# WIFI-BT.net
KiCad netlist of a schematic drawn in Altium Designer
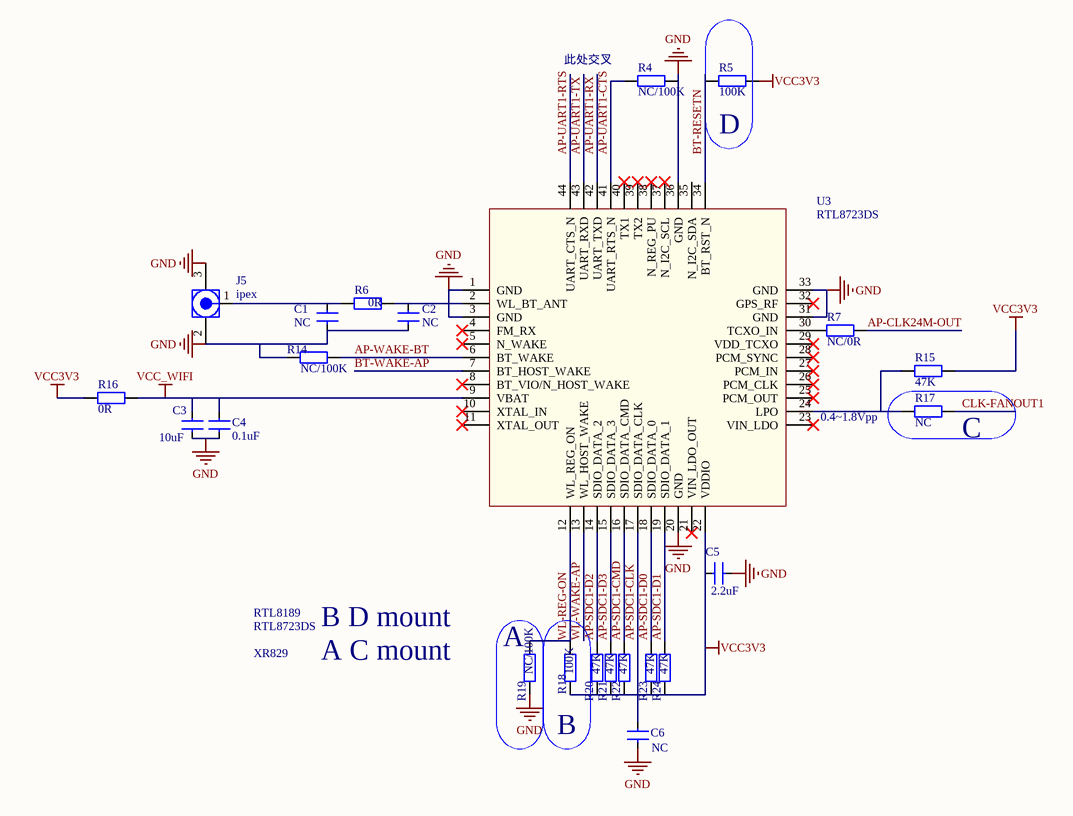
[diagram p0: WIFI-BT.SchDoc]

(export (version "E")
  (design (tool "Eeschema 10.0.6"))
  (components
    (comp (ref "C1")
      (value "NC")
      (footprint "C0402")
      (description "普通小电容")
      (libsource (lib "LIB_MANGO") (part "CAP"))
    )
    (comp (ref "C2")
      (value "NC")
      (footprint "C0402")
      (description "普通小电容")
      (libsource (lib "LIB_MANGO") (part "CAP"))
    )
    (comp (ref "C3")
      (value "10uF")
      (footprint "C0402")
      (description "普通小电容")
      (libsource (lib "LIB_MANGO") (part "CAP"))
    )
    (comp (ref "C4")
      (value "0.1uF")
      (footprint "C0402")
      (description "普通小电容")
      (libsource (lib "LIB_MANGO") (part "CAP"))
    )
    (comp (ref "C5")
      (value "2.2uF")
      (footprint "C0402")
      (description "普通小电容")
      (libsource (lib "LIB_MANGO") (part "CAP"))
    )
    (comp (ref "C6")
      (value "NC")
      (footprint "C0402")
      (description "普通小电容")
      (libsource (lib "LIB_MANGO") (part "CAP"))
    )
    (comp (ref "J5")
      (value "ipex")
      (footprint "I-PEX SOCKET")
      (libsource (lib "LIB_MANGO") (part "MCX_IPEX"))
    )
    (comp (ref "R4")
      (value "NC/100K")
      (footprint "R0402")
      (description "普通电阻")
      (libsource (lib "") (part "RES_1"))
    )
    (comp (ref "R5")
      (value "100K")
      (footprint "R0402")
      (description "普通电阻")
      (libsource (lib "") (part "RES_1"))
    )
    (comp (ref "R6")
      (value "0R")
      (footprint "R0402")
      (description "普通电阻")
      (libsource (lib "") (part "RES_2"))
    )
    (comp (ref "R7")
      (value "NC/0R")
      (footprint "R0402")
      (description "普通电阻")
      (libsource (lib "") (part "RES_2"))
    )
    (comp (ref "R14")
      (value "NC/100K")
      (footprint "R0402")
      (description "普通电阻")
      (libsource (lib "") (part "RES_2"))
    )
    (comp (ref "R15")
      (value "47K")
      (footprint "R0402")
      (description "普通电阻")
      (libsource (lib "LIB_MANGO") (part "RES"))
    )
    (comp (ref "R16")
      (value "0R")
      (footprint "R0402")
      (description "普通电阻")
      (libsource (lib "") (part "RES_2"))
    )
    (comp (ref "R17")
      (value "NC")
      (footprint "R0402")
      (description "普通电阻")
      (libsource (lib "") (part "RES_1"))
    )
    (comp (ref "R18")
      (value "100K")
      (footprint "R0402")
      (description "普通电阻")
      (libsource (lib "LIB_MANGO") (part "RES"))
    )
    (comp (ref "R19")
      (value "NC/100K")
      (footprint "R0402")
      (description "普通电阻")
      (libsource (lib "LIB_MANGO") (part "RES"))
    )
    (comp (ref "R20")
      (value "47K")
      (footprint "R0402")
      (description "普通电阻")
      (libsource (lib "LIB_MANGO") (part "RES"))
    )
    (comp (ref "R21")
      (value "47K")
      (footprint "R0402")
      (description "普通电阻")
      (libsource (lib "LIB_MANGO") (part "RES"))
    )
    (comp (ref "R22")
      (value "47K")
      (footprint "R0402")
      (description "普通电阻")
      (libsource (lib "LIB_MANGO") (part "RES"))
    )
    (comp (ref "R23")
      (value "47K")
      (footprint "R0402")
      (description "普通电阻")
      (libsource (lib "LIB_MANGO") (part "RES"))
    )
    (comp (ref "R24")
      (value "47K")
      (footprint "R0402")
      (description "普通电阻")
      (libsource (lib "LIB_MANGO") (part "RES"))
    )
    (comp (ref "U3") (value "RTL8723DS") (footprint "RTL8723DS") (libsource (lib "A") (part "AP6212")))
  )
  (nets
    (net (code "1") (name "/AP-CLK24M-OUT") (class "Default")
      (node (ref "R7") (pin "1") (pinfunction "1_1") (pintype "passive"))
    )
    (net (code "2") (name "/AP-SDC1-CLK") (class "Default")
      (node (ref "C6") (pin "2") (pinfunction "2_2") (pintype "passive"))
      (node (ref "U3") (pin "17") (pinfunction "SDIO_DATA_CLK_17") (pintype "passive"))
    )
    (net (code "3") (name "/AP-SDC1-CMD") (class "Default")
      (node (ref "R22") (pin "2") (pinfunction "2_2") (pintype "passive"))
      (node (ref "U3") (pin "16") (pinfunction "SDIO_DATA_CMD_16") (pintype "passive"))
    )
    (net (code "4") (name "/AP-SDC1-D0") (class "Default")
      (node (ref "R23") (pin "2") (pinfunction "2_2") (pintype "passive"))
      (node (ref "U3") (pin "18") (pinfunction "SDIO_DATA_0_18") (pintype "passive"))
    )
    (net (code "5") (name "/AP-SDC1-D1") (class "Default")
      (node (ref "R24") (pin "2") (pinfunction "2_2") (pintype "passive"))
      (node (ref "U3") (pin "19") (pinfunction "SDIO_DATA_1_19") (pintype "passive"))
    )
    (net (code "6") (name "/AP-SDC1-D2") (class "Default")
      (node (ref "R20") (pin "2") (pinfunction "2_2") (pintype "passive"))
      (node (ref "U3") (pin "14") (pinfunction "SDIO_DATA_2_14") (pintype "passive"))
    )
    (net (code "7") (name "/AP-SDC1-D3") (class "Default")
      (node (ref "R21") (pin "2") (pinfunction "2_2") (pintype "passive"))
      (node (ref "U3") (pin "15") (pinfunction "SDIO_DATA_3_15") (pintype "passive"))
    )
    (net (code "8") (name "/AP-UART1-CTS") (class "Default")
      (node (ref "R4") (pin "2") (pinfunction "2_2") (pintype "passive"))
      (node (ref "U3") (pin "41") (pinfunction "UART_RTS_N_41") (pintype "passive"))
    )
    (net (code "9") (name "/AP-UART1-RTS") (class "Default")
      (node (ref "U3") (pin "44") (pinfunction "UART_CTS_N_44") (pintype "passive"))
    )
    (net (code "10") (name "/AP-UART1-RX") (class "Default")
      (node (ref "U3") (pin "42") (pinfunction "UART_TXD_42") (pintype "passive"))
    )
    (net (code "11") (name "/AP-UART1-TX") (class "Default")
      (node (ref "U3") (pin "43") (pinfunction "UART_RXD_43") (pintype "passive"))
    )
    (net (code "12") (name "/AP-WAKE-BT") (class "Default")
      (node (ref "R14") (pin "1") (pinfunction "1_1") (pintype "passive"))
      (node (ref "U3") (pin "6") (pinfunction "BT_WAKE_6") (pintype "passive"))
    )
    (net (code "13") (name "/BT-RESETN") (class "Default")
      (node (ref "R5") (pin "2") (pinfunction "2_2") (pintype "passive"))
      (node (ref "U3") (pin "34") (pinfunction "BT_RST_N_34") (pintype "passive"))
    )
    (net (code "14") (name "/BT-WAKE-AP") (class "Default")
      (node (ref "U3") (pin "7") (pinfunction "BT_HOST_WAKE_7") (pintype "passive"))
    )
    (net (code "15") (name "/CLK-FANOUT1") (class "Default")
      (node (ref "R17") (pin "1") (pinfunction "1_1") (pintype "passive"))
    )
    (net (code "16") (name "/WL-REG-ON") (class "Default")
      (node (ref "R18") (pin "2") (pinfunction "2_2") (pintype "passive"))
      (node (ref "R19") (pin "2") (pinfunction "2_2") (pintype "passive"))
      (node (ref "U3") (pin "12") (pinfunction "WL_REG_ON_12") (pintype "passive"))
    )
    (net (code "17") (name "/WL-WAKE-AP") (class "Default")
      (node (ref "U3") (pin "13") (pinfunction "WL_HOST_WAKE_13") (pintype "passive"))
    )
    (net (code "18") (name "GND") (class "Default")
      (node (ref "C1") (pin "1") (pinfunction "1_1") (pintype "passive"))
      (node (ref "C2") (pin "1") (pinfunction "1_1") (pintype "passive"))
      (node (ref "C3") (pin "1") (pinfunction "1_1") (pintype "passive"))
      (node (ref "C4") (pin "1") (pinfunction "1_1") (pintype "passive"))
      (node (ref "C5") (pin "1") (pinfunction "1_1") (pintype "passive"))
      (node (ref "C6") (pin "1") (pinfunction "1_1") (pintype "passive"))
      (node (ref "J5") (pin "2") (pinfunction "GND_2") (pintype "power_in"))
      (node (ref "J5") (pin "3") (pinfunction "GND_3") (pintype "power_in"))
      (node (ref "R14") (pin "2") (pinfunction "2_2") (pintype "passive"))
      (node (ref "R19") (pin "1") (pinfunction "1_1") (pintype "passive"))
      (node (ref "R4") (pin "1") (pinfunction "1_1") (pintype "passive"))
      (node (ref "U3") (pin "1") (pinfunction "GND_1") (pintype "passive"))
      (node (ref "U3") (pin "20") (pinfunction "GND_20") (pintype "passive"))
      (node (ref "U3") (pin "3") (pinfunction "GND_3") (pintype "passive"))
      (node (ref "U3") (pin "31") (pinfunction "GND_31") (pintype "passive"))
      (node (ref "U3") (pin "33") (pinfunction "GND_33") (pintype "passive"))
      (node (ref "U3") (pin "36") (pinfunction "GND_36") (pintype "passive"))
    )
    (net (code "19") (name "Net-(J5-Signal)") (class "Default")
      (node (ref "C1") (pin "2") (pinfunction "2_2") (pintype "passive"))
      (node (ref "J5") (pin "1") (pinfunction "Signal_1") (pintype "passive"))
      (node (ref "R6") (pin "2") (pinfunction "2_2") (pintype "passive"))
    )
    (net (code "20") (name "Net-(U3-LPO)") (class "Default")
      (node (ref "R15") (pin "1") (pinfunction "1_1") (pintype "passive"))
      (node (ref "R17") (pin "2") (pinfunction "2_2") (pintype "passive"))
      (node (ref "U3") (pin "24") (pinfunction "LPO_24") (pintype "passive"))
    )
    (net (code "21") (name "Net-(U3-TCXO_IN)") (class "Default")
      (node (ref "R7") (pin "2") (pinfunction "2_2") (pintype "passive"))
      (node (ref "U3") (pin "30") (pinfunction "TCXO_IN_30") (pintype "passive"))
    )
    (net (code "22") (name "Net-(U3-WL_BT_ANT)") (class "Default")
      (node (ref "C2") (pin "2") (pinfunction "2_2") (pintype "passive"))
      (node (ref "R6") (pin "1") (pinfunction "1_1") (pintype "passive"))
      (node (ref "U3") (pin "2") (pinfunction "WL_BT_ANT_2") (pintype "passive"))
    )
    (net (code "23") (name "VCC3V3") (class "Default")
      (node (ref "C5") (pin "2") (pinfunction "2_2") (pintype "passive"))
      (node (ref "R15") (pin "2") (pinfunction "2_2") (pintype "passive"))
      (node (ref "R16") (pin "2") (pinfunction "2_2") (pintype "passive"))
      (node (ref "R18") (pin "1") (pinfunction "1_1") (pintype "passive"))
      (node (ref "R20") (pin "1") (pinfunction "1_1") (pintype "passive"))
      (node (ref "R21") (pin "1") (pinfunction "1_1") (pintype "passive"))
      (node (ref "R22") (pin "1") (pinfunction "1_1") (pintype "passive"))
      (node (ref "R23") (pin "1") (pinfunction "1_1") (pintype "passive"))
      (node (ref "R24") (pin "1") (pinfunction "1_1") (pintype "passive"))
      (node (ref "R5") (pin "1") (pinfunction "1_1") (pintype "passive"))
      (node (ref "U3") (pin "22") (pinfunction "VDDIO_22") (pintype "passive"))
    )
    (net (code "24") (name "VCC_WIFI") (class "Default")
      (node (ref "C3") (pin "2") (pinfunction "2_2") (pintype "passive"))
      (node (ref "C4") (pin "2") (pinfunction "2_2") (pintype "passive"))
      (node (ref "R16") (pin "1") (pinfunction "1_1") (pintype "passive"))
      (node (ref "U3") (pin "9") (pinfunction "VBAT_9") (pintype "passive"))
    )
    (net (code "25") (name "unconnected-(U3-BT_VIO{slash}N_HOST_WAKE-Pad8)") (class "Default")
      (node (ref "U3") (pin "8") (pinfunction "BT_VIO/N_HOST_WAKE_8") (pintype "passive+no_connect"))
    )
    (net (code "26") (name "unconnected-(U3-FM_RX-Pad4)") (class "Default")
      (node (ref "U3") (pin "4") (pinfunction "FM_RX_4") (pintype "passive+no_connect"))
    )
    (net (code "27") (name "unconnected-(U3-GPS_RF-Pad32)") (class "Default")
      (node (ref "U3") (pin "32") (pinfunction "GPS_RF_32") (pintype "passive+no_connect"))
    )
    (net (code "28") (name "unconnected-(U3-N_I2C_SCL-Pad37)") (class "Default")
      (node (ref "U3") (pin "37") (pinfunction "N_I2C_SCL_37") (pintype "passive+no_connect"))
    )
    (net (code "29") (name "unconnected-(U3-N_I2C_SDA-Pad35)") (class "Default")
      (node (ref "U3") (pin "35") (pinfunction "N_I2C_SDA_35") (pintype "passive"))
    )
    (net (code "30") (name "unconnected-(U3-N_REG_PU-Pad38)") (class "Default")
      (node (ref "U3") (pin "38") (pinfunction "N_REG_PU_38") (pintype "passive+no_connect"))
    )
    (net (code "31") (name "unconnected-(U3-N_WAKE-Pad5)") (class "Default")
      (node (ref "U3") (pin "5") (pinfunction "N_WAKE_5") (pintype "passive+no_connect"))
    )
    (net (code "32") (name "unconnected-(U3-PCM_CLK-Pad26)") (class "Default")
      (node (ref "U3") (pin "26") (pinfunction "PCM_CLK_26") (pintype "passive+no_connect"))
    )
    (net (code "33") (name "unconnected-(U3-PCM_IN-Pad27)") (class "Default")
      (node (ref "U3") (pin "27") (pinfunction "PCM_IN_27") (pintype "passive+no_connect"))
    )
    (net (code "34") (name "unconnected-(U3-PCM_OUT-Pad25)") (class "Default")
      (node (ref "U3") (pin "25") (pinfunction "PCM_OUT_25") (pintype "passive+no_connect"))
    )
    (net (code "35") (name "unconnected-(U3-PCM_SYNC-Pad28)") (class "Default")
      (node (ref "U3") (pin "28") (pinfunction "PCM_SYNC_28") (pintype "passive+no_connect"))
    )
    (net (code "36") (name "unconnected-(U3-TX1-Pad40)") (class "Default")
      (node (ref "U3") (pin "40") (pinfunction "TX1_40") (pintype "passive+no_connect"))
    )
    (net (code "37") (name "unconnected-(U3-TX2-Pad39)") (class "Default")
      (node (ref "U3") (pin "39") (pinfunction "TX2_39") (pintype "passive+no_connect"))
    )
    (net (code "38") (name "unconnected-(U3-VDD_TCXO-Pad29)") (class "Default")
      (node (ref "U3") (pin "29") (pinfunction "VDD_TCXO_29") (pintype "passive+no_connect"))
    )
    (net (code "39") (name "unconnected-(U3-VIN_LDO-Pad23)") (class "Default")
      (node (ref "U3") (pin "23") (pinfunction "VIN_LDO_23") (pintype "passive+no_connect"))
    )
    (net (code "40") (name "unconnected-(U3-VIN_LDO_OUT-Pad21)") (class "Default")
      (node (ref "U3") (pin "21") (pinfunction "VIN_LDO_OUT_21") (pintype "passive+no_connect"))
    )
    (net (code "41") (name "unconnected-(U3-XTAL_IN-Pad10)") (class "Default")
      (node (ref "U3") (pin "10") (pinfunction "XTAL_IN_10") (pintype "passive+no_connect"))
    )
    (net (code "42") (name "unconnected-(U3-XTAL_OUT-Pad11)") (class "Default")
      (node (ref "U3") (pin "11") (pinfunction "XTAL_OUT_11") (pintype "passive+no_connect"))
    )
  )
)
